# v3r01-carb-sync-shield.net
KiCad netlist of a schematic drawn in EAGLE
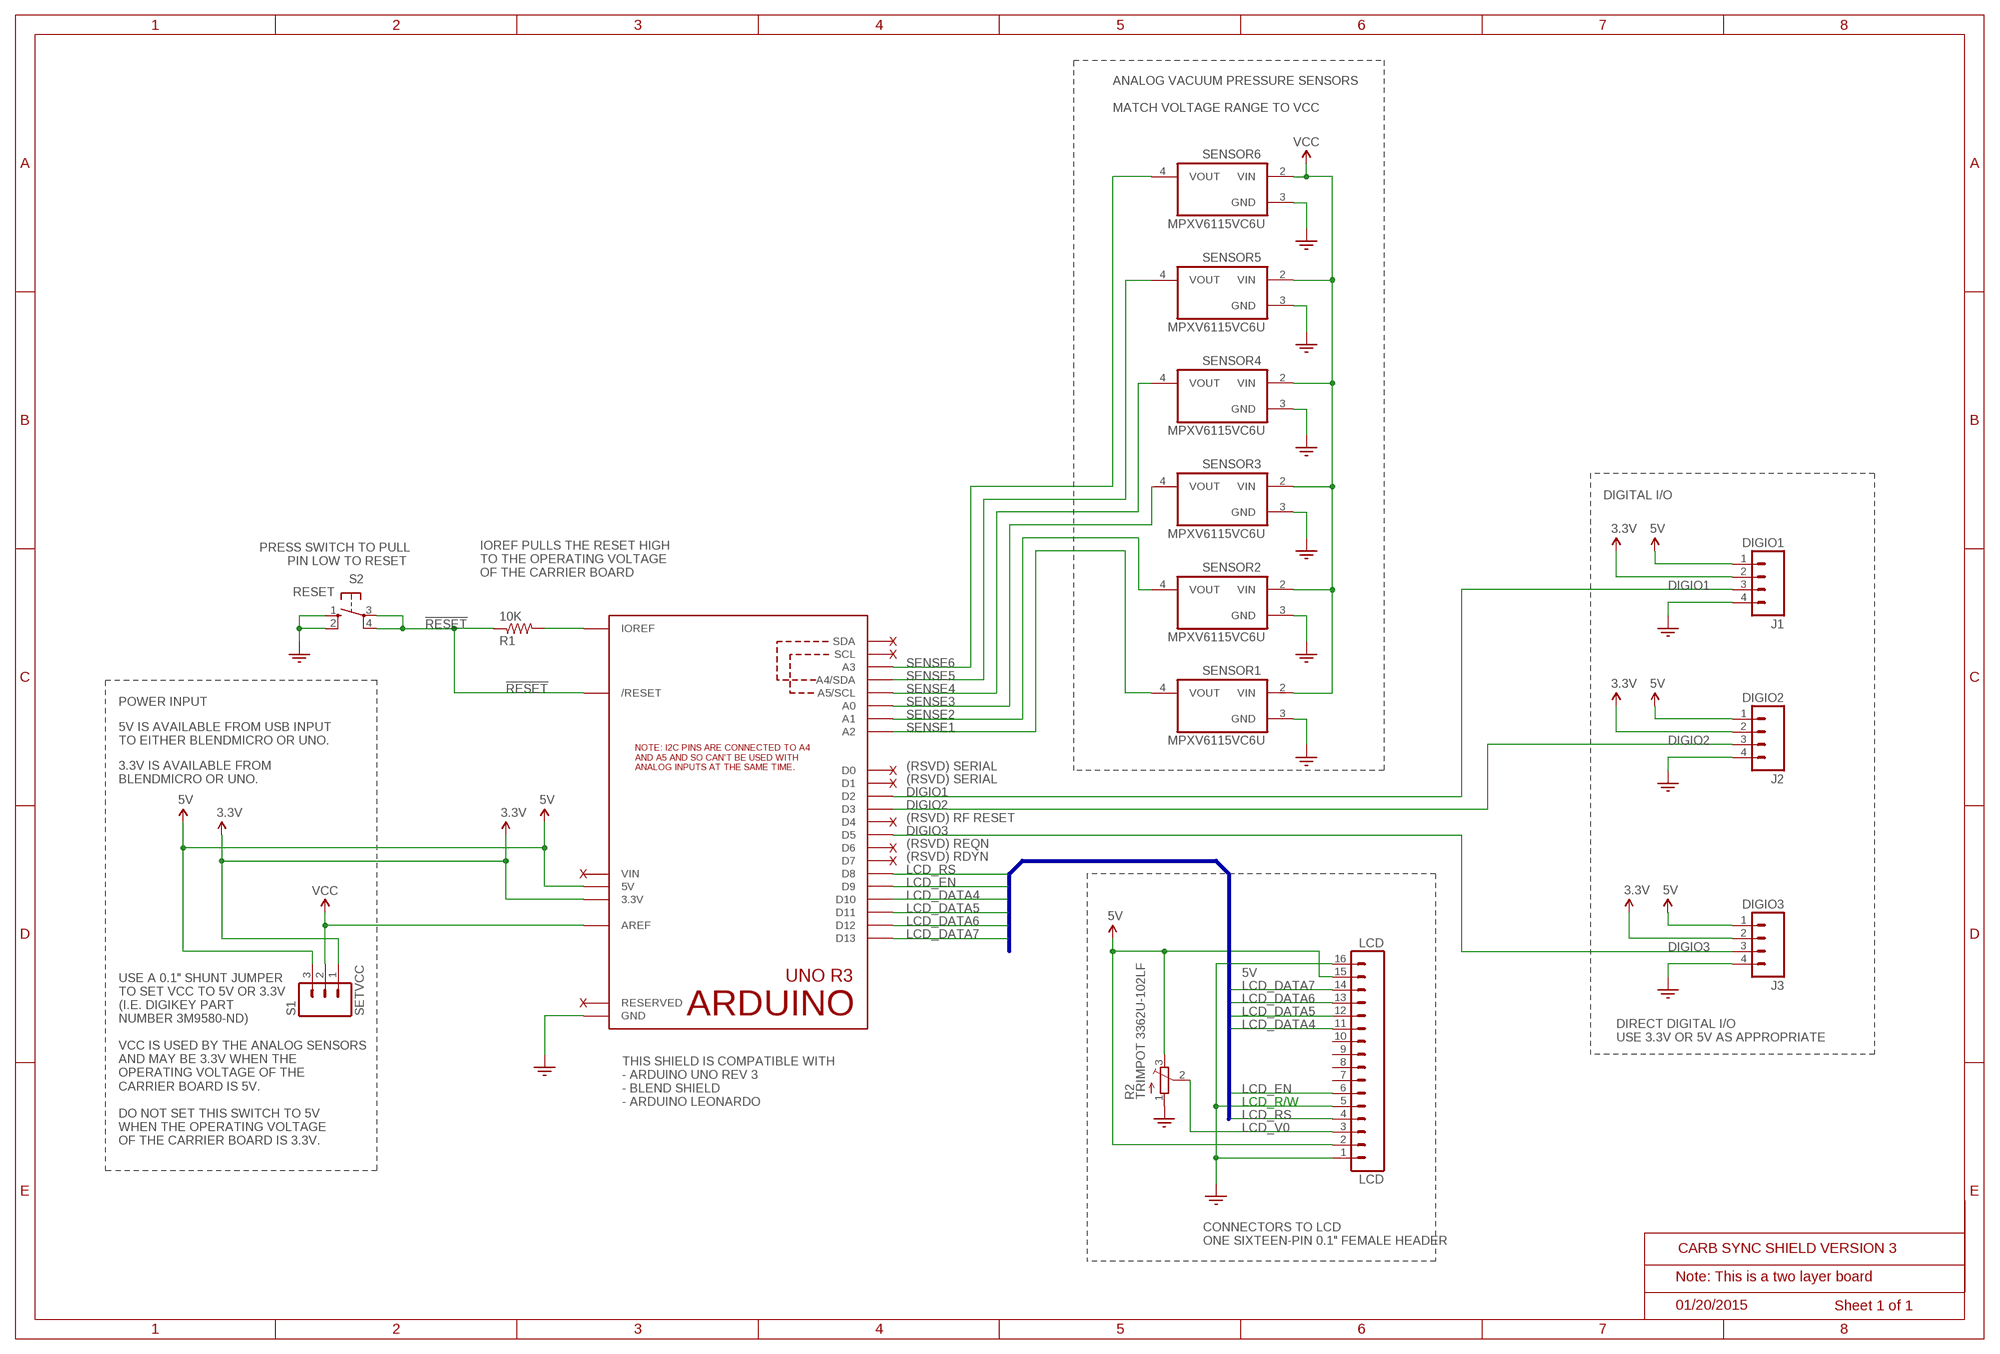
[diagram p0: schematic, sheet 1]

(export (version "E")
  (design (tool "Eeschema 10.0.6"))
  (components
    (comp (ref "J1")
      (value "DIGIO1")
      (footprint "eagle-import:1X04_LONGPADS")
      (libsource (lib "eagle-import") (part "M04LONGPADS"))
    )
    (comp (ref "J2")
      (value "DIGIO2")
      (footprint "eagle-import:1X04_LONGPADS")
      (libsource (lib "eagle-import") (part "M04LONGPADS"))
    )
    (comp (ref "J3")
      (value "DIGIO3")
      (footprint "eagle-import:1X04_LONGPADS")
      (libsource (lib "eagle-import") (part "M04LONGPADS"))
    )
    (comp (ref "LCD")
      (value "LCD")
      (footprint "eagle-import:CARBSYNCSHIELD_LCD")
      (libsource (lib "eagle-import") (part "CARBSYNCSHIELD_LCD"))
    )
    (comp (ref "R1")
      (value "10K")
      (footprint "eagle-import:0411_12")
      (libsource (lib "eagle-import") (part "R-US_0411/12"))
    )
    (comp (ref "R2")
      (value "TRIMPOT 3362U-102LF")
      (footprint "eagle-import:TRIM-3386")
      (libsource (lib "eagle-import") (part "TRIMPOT3386"))
    )
    (comp (ref "S1")
      (value "SETVCC")
      (footprint "eagle-import:1X03_LONGPADS")
      (libsource (lib "eagle-import") (part "M03LONGPADS"))
    )
    (comp (ref "S2")
      (value "RESET")
      (footprint "eagle-import:B3F-10XX")
      (fields (field (name "MPN") "B3F-1000"))
      (libsource (lib "eagle-import") (part "10-XX"))
    )
    (comp (ref "SENSOR1")
      (value "MPXV6115VC6U")
      (footprint "eagle-import:MPXV6115VC6U_T1-CASE482A")
      (libsource (lib "eagle-import") (part "MPXV6115VC6U"))
    )
    (comp (ref "SENSOR2")
      (value "MPXV6115VC6U")
      (footprint "eagle-import:MPXV6115VC6U_T1-CASE482A")
      (libsource (lib "eagle-import") (part "MPXV6115VC6U"))
    )
    (comp (ref "SENSOR3")
      (value "MPXV6115VC6U")
      (footprint "eagle-import:MPXV6115VC6U_T1-CASE482A")
      (libsource (lib "eagle-import") (part "MPXV6115VC6U"))
    )
    (comp (ref "SENSOR4")
      (value "MPXV6115VC6U")
      (footprint "eagle-import:MPXV6115VC6U_T1-CASE482A")
      (libsource (lib "eagle-import") (part "MPXV6115VC6U"))
    )
    (comp (ref "SENSOR5")
      (value "MPXV6115VC6U")
      (footprint "eagle-import:MPXV6115VC6U_T1-CASE482A")
      (libsource (lib "eagle-import") (part "MPXV6115VC6U"))
    )
    (comp (ref "SENSOR6")
      (value "MPXV6115VC6U")
      (footprint "eagle-import:MPXV6115VC6U_T1-CASE482A")
      (libsource (lib "eagle-import") (part "MPXV6115VC6U"))
    )
    (comp (ref "U$13")
      (value "ARDUINO-UNO-R3")
      (footprint "eagle-import:ARDUINO-UNO-R3-HOLES-NODIM")
      (libsource (lib "eagle-import") (part "ARDUINO-UNO-R3"))
    )
  )
  (nets
    (net (code "1") (name "/DIGIO1") (class "Default")
      (node (ref "J1") (pin "3") (pinfunction "3_3") (pintype "passive"))
      (node (ref "U$13") (pin "D2") (pinfunction "D2_D2") (pintype "bidirectional"))
    )
    (net (code "2") (name "/DIGIO2") (class "Default")
      (node (ref "J2") (pin "3") (pinfunction "3_3") (pintype "passive"))
      (node (ref "U$13") (pin "D3") (pinfunction "D3_D3") (pintype "bidirectional"))
    )
    (net (code "3") (name "/DIGIO3") (class "Default")
      (node (ref "J3") (pin "3") (pinfunction "3_3") (pintype "passive"))
      (node (ref "U$13") (pin "D5") (pinfunction "D5_D5") (pintype "bidirectional"))
    )
    (net (code "4") (name "/LCD_DATA4") (class "Default")
      (node (ref "LCD") (pin "11") (pinfunction "11_11") (pintype "passive"))
      (node (ref "U$13") (pin "D10") (pinfunction "D10_D10") (pintype "bidirectional"))
    )
    (net (code "5") (name "/LCD_DATA5") (class "Default")
      (node (ref "LCD") (pin "12") (pinfunction "12_12") (pintype "passive"))
      (node (ref "U$13") (pin "D11") (pinfunction "D11_D11") (pintype "bidirectional"))
    )
    (net (code "6") (name "/LCD_DATA6") (class "Default")
      (node (ref "LCD") (pin "13") (pinfunction "13_13") (pintype "passive"))
      (node (ref "U$13") (pin "D12") (pinfunction "D12_D12") (pintype "bidirectional"))
    )
    (net (code "7") (name "/LCD_DATA7") (class "Default")
      (node (ref "LCD") (pin "14") (pinfunction "14_14") (pintype "passive"))
      (node (ref "U$13") (pin "D13") (pinfunction "D13_D13") (pintype "bidirectional"))
    )
    (net (code "8") (name "/LCD_EN") (class "Default")
      (node (ref "LCD") (pin "6") (pinfunction "6_6") (pintype "passive"))
      (node (ref "U$13") (pin "D9") (pinfunction "D9_D9") (pintype "bidirectional"))
    )
    (net (code "9") (name "/LCD_RS") (class "Default")
      (node (ref "LCD") (pin "4") (pinfunction "4_4") (pintype "passive"))
      (node (ref "U$13") (pin "D8") (pinfunction "D8_D8") (pintype "bidirectional"))
    )
    (net (code "10") (name "/LCD_V0") (class "Default")
      (node (ref "LCD") (pin "3") (pinfunction "3_3") (pintype "passive"))
      (node (ref "R2") (pin "2") (pinfunction "S_2") (pintype "passive"))
    )
    (net (code "11") (name "/SENSE1") (class "Default")
      (node (ref "SENSOR1") (pin "4") (pinfunction "VOUT_4") (pintype "bidirectional"))
      (node (ref "U$13") (pin "A2") (pinfunction "A2_A2") (pintype "bidirectional"))
    )
    (net (code "12") (name "/SENSE2") (class "Default")
      (node (ref "SENSOR2") (pin "4") (pinfunction "VOUT_4") (pintype "bidirectional"))
      (node (ref "U$13") (pin "A1") (pinfunction "A1_A1") (pintype "bidirectional"))
    )
    (net (code "13") (name "/SENSE3") (class "Default")
      (node (ref "SENSOR3") (pin "4") (pinfunction "VOUT_4") (pintype "bidirectional"))
      (node (ref "U$13") (pin "A0") (pinfunction "A0_A0") (pintype "bidirectional"))
    )
    (net (code "14") (name "/SENSE4") (class "Default")
      (node (ref "SENSOR4") (pin "4") (pinfunction "VOUT_4") (pintype "bidirectional"))
      (node (ref "U$13") (pin "A5") (pinfunction "A5/SCL_A5") (pintype "bidirectional"))
    )
    (net (code "15") (name "/SENSE5") (class "Default")
      (node (ref "SENSOR5") (pin "4") (pinfunction "VOUT_4") (pintype "bidirectional"))
      (node (ref "U$13") (pin "A4") (pinfunction "A4/SDA_A4") (pintype "bidirectional"))
    )
    (net (code "16") (name "/SENSE6") (class "Default")
      (node (ref "SENSOR6") (pin "4") (pinfunction "VOUT_4") (pintype "bidirectional"))
      (node (ref "U$13") (pin "A3") (pinfunction "A3_A3") (pintype "bidirectional"))
    )
    (net (code "17") (name "/VIN") (class "Default")
      (node (ref "U$13") (pin "VIN") (pinfunction "VIN_VIN") (pintype "power_in"))
    )
    (net (code "18") (name "/~{RESET}") (class "Default")
      (node (ref "R1") (pin "1") (pinfunction "1_1") (pintype "passive"))
      (node (ref "S2") (pin "3") (pinfunction "P_3") (pintype "passive"))
      (node (ref "S2") (pin "4") (pinfunction "P1_4") (pintype "passive"))
      (node (ref "U$13") (pin "RESET") (pinfunction "/RESET_RESET") (pintype "bidirectional"))
    )
    (net (code "19") (name "3.3V") (class "Default")
      (node (ref "J1") (pin "2") (pinfunction "2_2") (pintype "passive"))
      (node (ref "J2") (pin "2") (pinfunction "2_2") (pintype "passive"))
      (node (ref "J3") (pin "2") (pinfunction "2_2") (pintype "passive"))
      (node (ref "S1") (pin "1") (pinfunction "1_1") (pintype "passive"))
      (node (ref "U$13") (pin "3V") (pinfunction "3.3V_3V") (pintype "power_in"))
    )
    (net (code "20") (name "5V") (class "Default")
      (node (ref "J1") (pin "1") (pinfunction "1_1") (pintype "passive"))
      (node (ref "J2") (pin "1") (pinfunction "1_1") (pintype "passive"))
      (node (ref "J3") (pin "1") (pinfunction "1_1") (pintype "passive"))
      (node (ref "LCD") (pin "15") (pinfunction "15_15") (pintype "passive"))
      (node (ref "LCD") (pin "2") (pinfunction "2_2") (pintype "passive"))
      (node (ref "R2") (pin "3") (pinfunction "E_3") (pintype "passive"))
      (node (ref "S1") (pin "3") (pinfunction "3_3") (pintype "passive"))
      (node (ref "U$13") (pin "5V") (pinfunction "5V_5V") (pintype "power_in"))
    )
    (net (code "21") (name "GND") (class "Default")
      (node (ref "J1") (pin "4") (pinfunction "4_4") (pintype "passive"))
      (node (ref "J2") (pin "4") (pinfunction "4_4") (pintype "passive"))
      (node (ref "J3") (pin "4") (pinfunction "4_4") (pintype "passive"))
      (node (ref "LCD") (pin "1") (pinfunction "1_1") (pintype "passive"))
      (node (ref "LCD") (pin "16") (pinfunction "16_16") (pintype "passive"))
      (node (ref "LCD") (pin "5") (pinfunction "5_5") (pintype "passive"))
      (node (ref "R2") (pin "1") (pinfunction "A_1") (pintype "passive"))
      (node (ref "S2") (pin "1") (pinfunction "S_1") (pintype "passive"))
      (node (ref "S2") (pin "2") (pinfunction "S1_2") (pintype "passive"))
      (node (ref "SENSOR1") (pin "3") (pinfunction "GND_3") (pintype "bidirectional"))
      (node (ref "SENSOR2") (pin "3") (pinfunction "GND_3") (pintype "bidirectional"))
      (node (ref "SENSOR3") (pin "3") (pinfunction "GND_3") (pintype "bidirectional"))
      (node (ref "SENSOR4") (pin "3") (pinfunction "GND_3") (pintype "bidirectional"))
      (node (ref "SENSOR5") (pin "3") (pinfunction "GND_3") (pintype "bidirectional"))
      (node (ref "SENSOR6") (pin "3") (pinfunction "GND_3") (pintype "bidirectional"))
      (node (ref "U$13") (pin "GND") (pinfunction "GND_GND") (pintype "power_in"))
      (node (ref "U$13") (pin "GND1") (pinfunction "GND_GND1") (pintype "power_in"))
      (node (ref "U$13") (pin "GND2") (pinfunction "GND_GND2") (pintype "power_in"))
    )
    (net (code "22") (name "Net-(R1-Pad2)") (class "Default")
      (node (ref "R1") (pin "2") (pinfunction "2_2") (pintype "passive"))
      (node (ref "U$13") (pin "IOREF") (pinfunction "IOREF_IOREF") (pintype "output"))
    )
    (net (code "23") (name "VCC") (class "Default")
      (node (ref "S1") (pin "2") (pinfunction "2_2") (pintype "passive"))
      (node (ref "SENSOR1") (pin "2") (pinfunction "VIN_2") (pintype "bidirectional"))
      (node (ref "SENSOR2") (pin "2") (pinfunction "VIN_2") (pintype "bidirectional"))
      (node (ref "SENSOR3") (pin "2") (pinfunction "VIN_2") (pintype "bidirectional"))
      (node (ref "SENSOR4") (pin "2") (pinfunction "VIN_2") (pintype "bidirectional"))
      (node (ref "SENSOR5") (pin "2") (pinfunction "VIN_2") (pintype "bidirectional"))
      (node (ref "SENSOR6") (pin "2") (pinfunction "VIN_2") (pintype "bidirectional"))
      (node (ref "U$13") (pin "AREF") (pinfunction "AREF_AREF") (pintype "bidirectional"))
    )
    (net (code "24") (name "unconnected-(LCD-Pad7)") (class "Default")
      (node (ref "LCD") (pin "7") (pinfunction "7_7") (pintype "passive"))
    )
    (net (code "25") (name "unconnected-(LCD-Pad8)") (class "Default")
      (node (ref "LCD") (pin "8") (pinfunction "8_8") (pintype "passive"))
    )
    (net (code "26") (name "unconnected-(LCD-Pad9)") (class "Default")
      (node (ref "LCD") (pin "9") (pinfunction "9_9") (pintype "passive"))
    )
    (net (code "27") (name "unconnected-(LCD-Pad10)") (class "Default")
      (node (ref "LCD") (pin "10") (pinfunction "10_10") (pintype "passive"))
    )
    (net (code "28") (name "unconnected-(U$13-PadD0)") (class "Default")
      (node (ref "U$13") (pin "D0") (pinfunction "D0_D0") (pintype "bidirectional"))
    )
    (net (code "29") (name "unconnected-(U$13-PadD1)") (class "Default")
      (node (ref "U$13") (pin "D1") (pinfunction "D1_D1") (pintype "bidirectional"))
    )
    (net (code "30") (name "unconnected-(U$13-PadD4)") (class "Default")
      (node (ref "U$13") (pin "D4") (pinfunction "D4_D4") (pintype "bidirectional"))
    )
    (net (code "31") (name "unconnected-(U$13-PadD6)") (class "Default")
      (node (ref "U$13") (pin "D6") (pinfunction "D6_D6") (pintype "bidirectional"))
    )
    (net (code "32") (name "unconnected-(U$13-PadD7)") (class "Default")
      (node (ref "U$13") (pin "D7") (pinfunction "D7_D7") (pintype "bidirectional"))
    )
    (net (code "33") (name "unconnected-(U$13-PadRESERVED)") (class "Default")
      (node (ref "U$13") (pin "RESERVED") (pinfunction "RESERVED_RESERVED") (pintype "no_connect"))
    )
    (net (code "34") (name "unconnected-(U$13-PadSCL)") (class "Default")
      (node (ref "U$13") (pin "SCL") (pinfunction "SCL_SCL") (pintype "bidirectional"))
    )
    (net (code "35") (name "unconnected-(U$13-PadSDA)") (class "Default")
      (node (ref "U$13") (pin "SDA") (pinfunction "SDA_SDA") (pintype "bidirectional"))
    )
  )
)
